# P02_MCU.net
KiCad netlist of a schematic drawn in Altium Designer
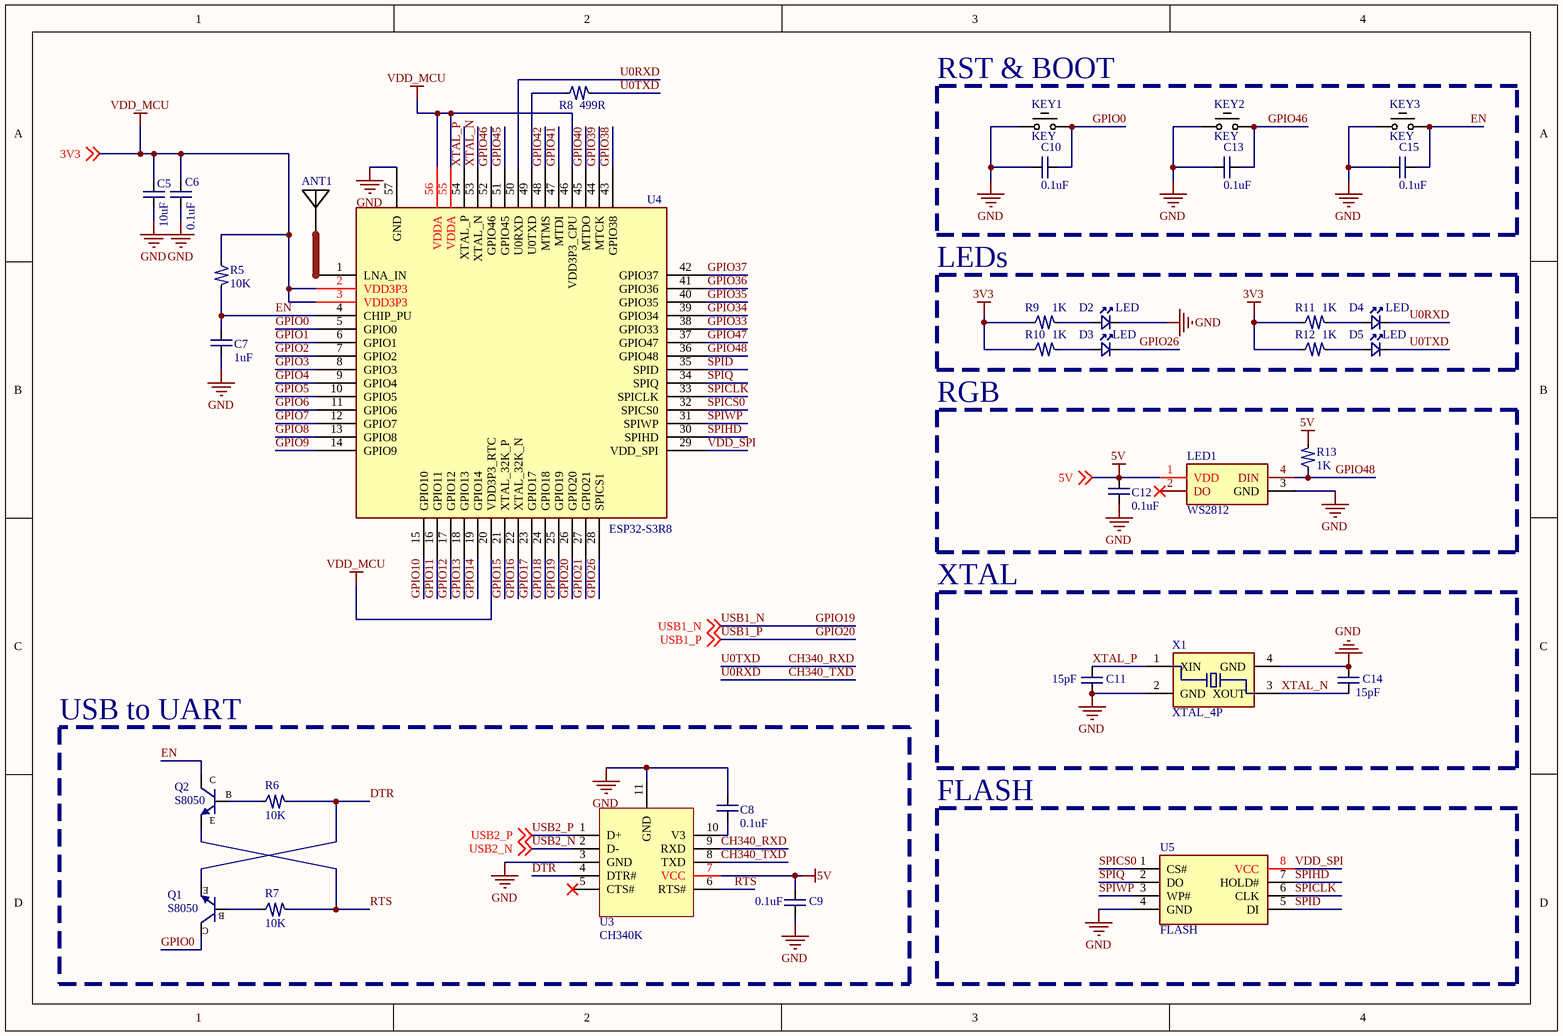
[diagram p0: P02_MCU.SchDoc]

(export (version "E")
  (design (tool "Eeschema 10.0.6"))
  (components
    (comp (ref "ANT1")
      (value "ANT")
      (footprint "CrossAir_CAC03")
      (description "天线")
      (libsource (lib "Schlib") (part "ANT"))
    )
    (comp (ref "C5")
      (value "10uF")
      (footprint "C_0402")
      (description "无极性电容")
      (libsource (lib "Schlib") (part "C"))
    )
    (comp (ref "C6")
      (value "0.1uF")
      (footprint "C_0402")
      (description "无极性电容")
      (libsource (lib "Schlib") (part "C"))
    )
    (comp (ref "C7")
      (value "1uF")
      (footprint "C_0402")
      (description "无极性电容")
      (libsource (lib "Schlib") (part "C"))
    )
    (comp (ref "C8")
      (value "0.1uF")
      (footprint "C_0603")
      (description "无极性电容")
      (libsource (lib "Schlib") (part "C"))
    )
    (comp (ref "C9")
      (value "0.1uF")
      (footprint "C_0603")
      (description "无极性电容")
      (libsource (lib "Schlib") (part "C"))
    )
    (comp (ref "C10")
      (value "0.1uF")
      (footprint "C_0603")
      (description "无极性电容")
      (libsource (lib "Schlib") (part "C"))
    )
    (comp (ref "C11")
      (value "15pF")
      (footprint "C_0402")
      (description "无极性电容")
      (libsource (lib "Schlib") (part "C"))
    )
    (comp (ref "C12")
      (value "0.1uF")
      (footprint "C_0603")
      (description "无极性电容")
      (libsource (lib "Schlib") (part "C"))
    )
    (comp (ref "C13")
      (value "0.1uF")
      (footprint "C_0603")
      (description "无极性电容")
      (libsource (lib "Schlib") (part "C"))
    )
    (comp (ref "C14")
      (value "15pF")
      (footprint "C_0402")
      (description "无极性电容")
      (libsource (lib "Schlib") (part "C"))
    )
    (comp (ref "C15")
      (value "0.1uF")
      (footprint "C_0603")
      (description "无极性电容")
      (libsource (lib "Schlib") (part "C"))
    )
    (comp (ref "D2")
      (value "LED")
      (footprint "LED_0603")
      (description "发光二极管")
      (libsource (lib "Schlib") (part "LED"))
    )
    (comp (ref "D3")
      (value "LED")
      (footprint "LED_0603")
      (description "发光二极管")
      (libsource (lib "Schlib") (part "LED"))
    )
    (comp (ref "D4")
      (value "LED")
      (footprint "LED_0603")
      (description "发光二极管")
      (libsource (lib "Schlib") (part "LED"))
    )
    (comp (ref "D5")
      (value "LED")
      (footprint "LED_0603")
      (description "发光二极管")
      (libsource (lib "Schlib") (part "LED"))
    )
    (comp (ref "KEY1")
      (value "KEY")
      (footprint "KEY")
      (description "通用2脚按键")
      (libsource (lib "Schlib") (part "KEY"))
    )
    (comp (ref "KEY2")
      (value "KEY")
      (footprint "KEY")
      (description "通用2脚按键")
      (libsource (lib "Schlib") (part "KEY"))
    )
    (comp (ref "KEY3")
      (value "KEY")
      (footprint "KEY")
      (description "通用2脚按键")
      (libsource (lib "Schlib") (part "KEY"))
    )
    (comp (ref "LED1")
      (value "WS2812")
      (footprint "SMD5050")
      (description "RGB")
      (libsource (lib "Schlib") (part "WS2812"))
    )
    (comp (ref "Q1")
      (value "S8050")
      (footprint "SOT-23-3")
      (description "三极管")
      (libsource (lib "Schlib") (part "NFET"))
    )
    (comp (ref "Q2")
      (value "S8050")
      (footprint "SOT-23-3")
      (description "三极管")
      (libsource (lib "Schlib") (part "NFET"))
    )
    (comp (ref "R5")
      (value "10K")
      (footprint "R_0402")
      (description "电阻")
      (libsource (lib "Schlib") (part "R"))
    )
    (comp (ref "R6")
      (value "10K")
      (footprint "R_0603")
      (description "电阻")
      (libsource (lib "Schlib") (part "R"))
    )
    (comp (ref "R7")
      (value "10K")
      (footprint "R_0603")
      (description "电阻")
      (libsource (lib "Schlib") (part "R"))
    )
    (comp (ref "R8")
      (value "499R")
      (footprint "R_0402")
      (description "电阻")
      (libsource (lib "Schlib") (part "R"))
    )
    (comp (ref "R9")
      (value "1K")
      (footprint "R_0603")
      (description "电阻")
      (libsource (lib "Schlib") (part "R"))
    )
    (comp (ref "R10")
      (value "1K")
      (footprint "R_0603")
      (description "电阻")
      (libsource (lib "Schlib") (part "R"))
    )
    (comp (ref "R11")
      (value "1K")
      (footprint "R_0603")
      (description "电阻")
      (libsource (lib "Schlib") (part "R"))
    )
    (comp (ref "R12")
      (value "1K")
      (footprint "R_0603")
      (description "电阻")
      (libsource (lib "Schlib") (part "R"))
    )
    (comp (ref "R13")
      (value "1K")
      (footprint "R_0603")
      (description "电阻")
      (libsource (lib "Schlib") (part "R"))
    )
    (comp (ref "U3")
      (value "CH340K")
      (footprint "ESOP-10")
      (description "USB-UART")
      (libsource (lib "Schlib") (part "CH340K"))
    )
    (comp (ref "U4")
      (value "ESP32-S3R8")
      (footprint "QFN-56")
      (libsource (lib "Schlib") (part "ESP32-S3FN8"))
    )
    (comp (ref "U5")
      (value "FLASH")
      (footprint "SOIC-8-208mil")
      (description "NOR FLASH")
      (libsource (lib "Schlib") (part "FLASH"))
    )
    (comp (ref "X1")
      (value "XTAL_4P")
      (footprint "X_SMD3225")
      (description "晶振 4P")
      (libsource (lib "Schlib") (part "XTAL_4P"))
    )
  )
  (nets
    (net (code "1") (name "/CH340_RXD") (class "Default")
      (node (ref "D5") (pin "1") (pinfunction "1_1") (pintype "passive"))
      (node (ref "R8") (pin "1") (pinfunction "1_1") (pintype "passive"))
      (node (ref "U3") (pin "9") (pinfunction "RXD_9") (pintype "passive"))
    )
    (net (code "2") (name "/CH340_TXD") (class "Default")
      (node (ref "D4") (pin "1") (pinfunction "1_1") (pintype "passive"))
      (node (ref "U3") (pin "8") (pinfunction "TXD_8") (pintype "passive"))
      (node (ref "U4") (pin "50") (pinfunction "U0RXD_50") (pintype "passive"))
    )
    (net (code "3") (name "/DTR") (class "Default")
      (node (ref "Q1") (pin "2") (pinfunction "E_2") (pintype "passive"))
      (node (ref "R6") (pin "1") (pinfunction "1_1") (pintype "passive"))
      (node (ref "U3") (pin "4") (pinfunction "DTR#_4") (pintype "passive"))
    )
    (net (code "4") (name "/EN") (class "Default")
      (node (ref "C15") (pin "1") (pinfunction "1_1") (pintype "passive"))
      (node (ref "C7") (pin "2") (pinfunction "2_2") (pintype "passive"))
      (node (ref "KEY3") (pin "1") (pinfunction "1_1") (pintype "passive"))
      (node (ref "Q2") (pin "3") (pinfunction "C_3") (pintype "passive"))
      (node (ref "R5") (pin "1") (pinfunction "1_1") (pintype "passive"))
      (node (ref "U4") (pin "4") (pinfunction "CHIP_PU_4") (pintype "passive"))
    )
    (net (code "5") (name "/GPIO0") (class "Default")
      (node (ref "C10") (pin "1") (pinfunction "1_1") (pintype "passive"))
      (node (ref "KEY1") (pin "1") (pinfunction "1_1") (pintype "passive"))
      (node (ref "Q1") (pin "3") (pinfunction "C_3") (pintype "passive"))
      (node (ref "U4") (pin "5") (pinfunction "GPIO0_5") (pintype "passive"))
    )
    (net (code "6") (name "/GPIO1") (class "Default")
      (node (ref "U4") (pin "6") (pinfunction "GPIO1_6") (pintype "passive"))
    )
    (net (code "7") (name "/GPIO2") (class "Default")
      (node (ref "U4") (pin "7") (pinfunction "GPIO2_7") (pintype "passive"))
    )
    (net (code "8") (name "/GPIO3") (class "Default")
      (node (ref "U4") (pin "8") (pinfunction "GPIO3_8") (pintype "passive"))
    )
    (net (code "9") (name "/GPIO4") (class "Default")
      (node (ref "U4") (pin "9") (pinfunction "GPIO4_9") (pintype "passive"))
    )
    (net (code "10") (name "/GPIO5") (class "Default")
      (node (ref "U4") (pin "10") (pinfunction "GPIO5_10") (pintype "passive"))
    )
    (net (code "11") (name "/GPIO6") (class "Default")
      (node (ref "U4") (pin "11") (pinfunction "GPIO6_11") (pintype "passive"))
    )
    (net (code "12") (name "/GPIO7") (class "Default")
      (node (ref "U4") (pin "12") (pinfunction "GPIO7_12") (pintype "passive"))
    )
    (net (code "13") (name "/GPIO8") (class "Default")
      (node (ref "U4") (pin "13") (pinfunction "GPIO8_13") (pintype "passive"))
    )
    (net (code "14") (name "/GPIO9") (class "Default")
      (node (ref "U4") (pin "14") (pinfunction "GPIO9_14") (pintype "passive"))
    )
    (net (code "15") (name "/GPIO10") (class "Default")
      (node (ref "U4") (pin "15") (pinfunction "GPIO10_15") (pintype "passive"))
    )
    (net (code "16") (name "/GPIO11") (class "Default")
      (node (ref "U4") (pin "16") (pinfunction "GPIO11_16") (pintype "passive"))
    )
    (net (code "17") (name "/GPIO12") (class "Default")
      (node (ref "U4") (pin "17") (pinfunction "GPIO12_17") (pintype "passive"))
    )
    (net (code "18") (name "/GPIO13") (class "Default")
      (node (ref "U4") (pin "18") (pinfunction "GPIO13_18") (pintype "passive"))
    )
    (net (code "19") (name "/GPIO14") (class "Default")
      (node (ref "U4") (pin "19") (pinfunction "GPIO14_19") (pintype "passive"))
    )
    (net (code "20") (name "/GPIO15") (class "Default")
      (node (ref "U4") (pin "21") (pinfunction "XTAL_32K_P_21") (pintype "passive"))
    )
    (net (code "21") (name "/GPIO16") (class "Default")
      (node (ref "U4") (pin "22") (pinfunction "XTAL_32K_N_22") (pintype "passive"))
    )
    (net (code "22") (name "/GPIO17") (class "Default")
      (node (ref "U4") (pin "23") (pinfunction "GPIO17_23") (pintype "passive"))
    )
    (net (code "23") (name "/GPIO18") (class "Default")
      (node (ref "U4") (pin "24") (pinfunction "GPIO18_24") (pintype "passive"))
    )
    (net (code "24") (name "/GPIO21") (class "Default")
      (node (ref "U4") (pin "27") (pinfunction "GPIO21_27") (pintype "passive"))
    )
    (net (code "25") (name "/GPIO26") (class "Default")
      (node (ref "D3") (pin "1") (pinfunction "1_1") (pintype "passive"))
      (node (ref "U4") (pin "28") (pinfunction "SPICS1_28") (pintype "passive"))
    )
    (net (code "26") (name "/GPIO33") (class "Default")
      (node (ref "U4") (pin "38") (pinfunction "GPIO33_38") (pintype "passive"))
    )
    (net (code "27") (name "/GPIO34") (class "Default")
      (node (ref "U4") (pin "39") (pinfunction "GPIO34_39") (pintype "passive"))
    )
    (net (code "28") (name "/GPIO35") (class "Default")
      (node (ref "U4") (pin "40") (pinfunction "GPIO35_40") (pintype "passive"))
    )
    (net (code "29") (name "/GPIO36") (class "Default")
      (node (ref "U4") (pin "41") (pinfunction "GPIO36_41") (pintype "passive"))
    )
    (net (code "30") (name "/GPIO37") (class "Default")
      (node (ref "U4") (pin "42") (pinfunction "GPIO37_42") (pintype "passive"))
    )
    (net (code "31") (name "/GPIO38") (class "Default")
      (node (ref "U4") (pin "43") (pinfunction "GPIO38_43") (pintype "passive"))
    )
    (net (code "32") (name "/GPIO39") (class "Default")
      (node (ref "U4") (pin "44") (pinfunction "MTCK_44") (pintype "passive"))
    )
    (net (code "33") (name "/GPIO40") (class "Default")
      (node (ref "U4") (pin "45") (pinfunction "MTDO_45") (pintype "passive"))
    )
    (net (code "34") (name "/GPIO41") (class "Default")
      (node (ref "U4") (pin "47") (pinfunction "MTDI_47") (pintype "passive"))
    )
    (net (code "35") (name "/GPIO42") (class "Default")
      (node (ref "U4") (pin "48") (pinfunction "MTMS_48") (pintype "passive"))
    )
    (net (code "36") (name "/GPIO45") (class "Default")
      (node (ref "U4") (pin "51") (pinfunction "GPIO45_51") (pintype "passive"))
    )
    (net (code "37") (name "/GPIO46") (class "Default")
      (node (ref "C13") (pin "1") (pinfunction "1_1") (pintype "passive"))
      (node (ref "KEY2") (pin "1") (pinfunction "1_1") (pintype "passive"))
      (node (ref "U4") (pin "52") (pinfunction "GPIO46_52") (pintype "passive"))
    )
    (net (code "38") (name "/GPIO47") (class "Default")
      (node (ref "U4") (pin "37") (pinfunction "GPIO47_37") (pintype "passive"))
    )
    (net (code "39") (name "/GPIO48") (class "Default")
      (node (ref "LED1") (pin "4") (pinfunction "DIN_4") (pintype "passive"))
      (node (ref "R13") (pin "2") (pinfunction "2_2") (pintype "passive"))
      (node (ref "U4") (pin "36") (pinfunction "GPIO48_36") (pintype "passive"))
    )
    (net (code "40") (name "/RTS") (class "Default")
      (node (ref "Q2") (pin "2") (pinfunction "E_2") (pintype "passive"))
      (node (ref "R7") (pin "1") (pinfunction "1_1") (pintype "passive"))
      (node (ref "U3") (pin "6") (pinfunction "RTS#_6") (pintype "passive"))
    )
    (net (code "41") (name "/SPICLK") (class "Default")
      (node (ref "U4") (pin "33") (pinfunction "SPICLK_33") (pintype "passive"))
      (node (ref "U5") (pin "6") (pinfunction "CLK_6") (pintype "passive"))
    )
    (net (code "42") (name "/SPICS0") (class "Default")
      (node (ref "U4") (pin "32") (pinfunction "SPICS0_32") (pintype "passive"))
      (node (ref "U5") (pin "1") (pinfunction "CS#_1") (pintype "passive"))
    )
    (net (code "43") (name "/SPID") (class "Default")
      (node (ref "U4") (pin "35") (pinfunction "SPID_35") (pintype "passive"))
      (node (ref "U5") (pin "5") (pinfunction "DI_5") (pintype "passive"))
    )
    (net (code "44") (name "/SPIHD") (class "Default")
      (node (ref "U4") (pin "30") (pinfunction "SPIHD_30") (pintype "passive"))
      (node (ref "U5") (pin "7") (pinfunction "HOLD#_7") (pintype "passive"))
    )
    (net (code "45") (name "/SPIQ") (class "Default")
      (node (ref "U4") (pin "34") (pinfunction "SPIQ_34") (pintype "passive"))
      (node (ref "U5") (pin "2") (pinfunction "DO_2") (pintype "passive"))
    )
    (net (code "46") (name "/SPIWP") (class "Default")
      (node (ref "U4") (pin "31") (pinfunction "SPIWP_31") (pintype "passive"))
      (node (ref "U5") (pin "3") (pinfunction "WP#_3") (pintype "passive"))
    )
    (net (code "47") (name "/VDD_SPI") (class "Default")
      (node (ref "U4") (pin "29") (pinfunction "VDD_SPI_29") (pintype "passive"))
      (node (ref "U5") (pin "8") (pinfunction "VCC_8") (pintype "passive"))
    )
    (net (code "48") (name "/XTAL_N") (class "Default")
      (node (ref "C14") (pin "1") (pinfunction "1_1") (pintype "passive"))
      (node (ref "U4") (pin "53") (pinfunction "XTAL_N_53") (pintype "passive"))
      (node (ref "X1") (pin "3") (pinfunction "XOUT_3") (pintype "passive"))
    )
    (net (code "49") (name "/XTAL_P") (class "Default")
      (node (ref "C11") (pin "2") (pinfunction "2_2") (pintype "passive"))
      (node (ref "U4") (pin "54") (pinfunction "XTAL_P_54") (pintype "passive"))
      (node (ref "X1") (pin "1") (pinfunction "XIN_1") (pintype "passive"))
    )
    (net (code "50") (name "3V3") (class "Default")
      (node (ref "C5") (pin "1") (pinfunction "1_1") (pintype "passive"))
      (node (ref "C6") (pin "1") (pinfunction "1_1") (pintype "passive"))
      (node (ref "R10") (pin "2") (pinfunction "2_2") (pintype "passive"))
      (node (ref "R11") (pin "2") (pinfunction "2_2") (pintype "passive"))
      (node (ref "R12") (pin "2") (pinfunction "2_2") (pintype "passive"))
      (node (ref "R5") (pin "2") (pinfunction "2_2") (pintype "passive"))
      (node (ref "R9") (pin "2") (pinfunction "2_2") (pintype "passive"))
      (node (ref "U4") (pin "2") (pinfunction "VDD3P3_2") (pintype "passive"))
      (node (ref "U4") (pin "20") (pinfunction "VDD3P3_RTC_20") (pintype "passive"))
      (node (ref "U4") (pin "3") (pinfunction "VDD3P3_3") (pintype "passive"))
      (node (ref "U4") (pin "46") (pinfunction "VDD3P3_CPU_46") (pintype "passive"))
      (node (ref "U4") (pin "55") (pinfunction "VDDA_55") (pintype "passive"))
      (node (ref "U4") (pin "56") (pinfunction "VDDA_56") (pintype "passive"))
    )
    (net (code "51") (name "5V") (class "Default")
      (node (ref "C12") (pin "2") (pinfunction "2_2") (pintype "passive"))
      (node (ref "C9") (pin "2") (pinfunction "2_2") (pintype "passive"))
      (node (ref "LED1") (pin "1") (pinfunction "VDD_1") (pintype "passive"))
      (node (ref "R13") (pin "1") (pinfunction "1_1") (pintype "passive"))
      (node (ref "U3") (pin "7") (pinfunction "VCC_7") (pintype "passive"))
    )
    (net (code "52") (name "GND") (class "Default")
      (node (ref "C10") (pin "2") (pinfunction "2_2") (pintype "passive"))
      (node (ref "C11") (pin "1") (pinfunction "1_1") (pintype "passive"))
      (node (ref "C12") (pin "1") (pinfunction "1_1") (pintype "passive"))
      (node (ref "C13") (pin "2") (pinfunction "2_2") (pintype "passive"))
      (node (ref "C14") (pin "2") (pinfunction "2_2") (pintype "passive"))
      (node (ref "C15") (pin "2") (pinfunction "2_2") (pintype "passive"))
      (node (ref "C5") (pin "2") (pinfunction "2_2") (pintype "passive"))
      (node (ref "C6") (pin "2") (pinfunction "2_2") (pintype "passive"))
      (node (ref "C7") (pin "1") (pinfunction "1_1") (pintype "passive"))
      (node (ref "C8") (pin "1") (pinfunction "1_1") (pintype "passive"))
      (node (ref "C9") (pin "1") (pinfunction "1_1") (pintype "passive"))
      (node (ref "D2") (pin "1") (pinfunction "1_1") (pintype "passive"))
      (node (ref "KEY1") (pin "2") (pinfunction "2_2") (pintype "passive"))
      (node (ref "KEY2") (pin "2") (pinfunction "2_2") (pintype "passive"))
      (node (ref "KEY3") (pin "2") (pinfunction "2_2") (pintype "passive"))
      (node (ref "LED1") (pin "3") (pinfunction "GND_3") (pintype "passive"))
      (node (ref "U3") (pin "11") (pinfunction "GND_11") (pintype "passive"))
      (node (ref "U3") (pin "3") (pinfunction "GND_3") (pintype "passive"))
      (node (ref "U4") (pin "57") (pinfunction "GND_57") (pintype "passive"))
      (node (ref "U5") (pin "4") (pinfunction "GND_4") (pintype "passive"))
      (node (ref "X1") (pin "2") (pinfunction "GND_2") (pintype "passive"))
      (node (ref "X1") (pin "4") (pinfunction "GND_4") (pintype "passive"))
    )
    (net (code "53") (name "Net-(ANT1-Feed)") (class "Default")
      (node (ref "ANT1") (pin "1") (pinfunction "Feed_1") (pintype "passive"))
      (node (ref "U4") (pin "1") (pinfunction "LNA_IN_1") (pintype "passive"))
    )
    (net (code "54") (name "Net-(D2-Pad2)") (class "Default")
      (node (ref "D2") (pin "2") (pinfunction "2_2") (pintype "passive"))
      (node (ref "R9") (pin "1") (pinfunction "1_1") (pintype "passive"))
    )
    (net (code "55") (name "Net-(D3-Pad2)") (class "Default")
      (node (ref "D3") (pin "2") (pinfunction "2_2") (pintype "passive"))
      (node (ref "R10") (pin "1") (pinfunction "1_1") (pintype "passive"))
    )
    (net (code "56") (name "Net-(D4-Pad2)") (class "Default")
      (node (ref "D4") (pin "2") (pinfunction "2_2") (pintype "passive"))
      (node (ref "R11") (pin "1") (pinfunction "1_1") (pintype "passive"))
    )
    (net (code "57") (name "Net-(D5-Pad2)") (class "Default")
      (node (ref "D5") (pin "2") (pinfunction "2_2") (pintype "passive"))
      (node (ref "R12") (pin "1") (pinfunction "1_1") (pintype "passive"))
    )
    (net (code "58") (name "Net-(Q1-B)") (class "Default")
      (node (ref "Q1") (pin "1") (pinfunction "B_1") (pintype "passive"))
      (node (ref "R7") (pin "2") (pinfunction "2_2") (pintype "passive"))
    )
    (net (code "59") (name "Net-(Q2-B)") (class "Default")
      (node (ref "Q2") (pin "1") (pinfunction "B_1") (pintype "passive"))
      (node (ref "R6") (pin "2") (pinfunction "2_2") (pintype "passive"))
    )
    (net (code "60") (name "Net-(U3-V3)") (class "Default")
      (node (ref "C8") (pin "2") (pinfunction "2_2") (pintype "passive"))
      (node (ref "U3") (pin "10") (pinfunction "V3_10") (pintype "passive"))
    )
    (net (code "61") (name "Net-(U4-U0TXD)") (class "Default")
      (node (ref "R8") (pin "2") (pinfunction "2_2") (pintype "passive"))
      (node (ref "U4") (pin "49") (pinfunction "U0TXD_49") (pintype "passive"))
    )
    (net (code "62") (name "USB1_N") (class "Default")
      (node (ref "U4") (pin "25") (pinfunction "GPIO19_25") (pintype "passive"))
    )
    (net (code "63") (name "USB1_P") (class "Default")
      (node (ref "U4") (pin "26") (pinfunction "GPIO20_26") (pintype "passive"))
    )
    (net (code "64") (name "USB2_N") (class "Default")
      (node (ref "U3") (pin "2") (pinfunction "D-_2") (pintype "passive"))
    )
    (net (code "65") (name "USB2_P") (class "Default")
      (node (ref "U3") (pin "1") (pinfunction "D+_1") (pintype "passive"))
    )
    (net (code "66") (name "unconnected-(LED1-DO-Pad2)") (class "Default")
      (node (ref "LED1") (pin "2") (pinfunction "DO_2") (pintype "passive+no_connect"))
    )
    (net (code "67") (name "unconnected-(U3-CTS#-Pad5)") (class "Default")
      (node (ref "U3") (pin "5") (pinfunction "CTS#_5") (pintype "passive+no_connect"))
    )
  )
)
